# NKK_DOF.net
KiCad netlist of a schematic drawn in Altium Designer
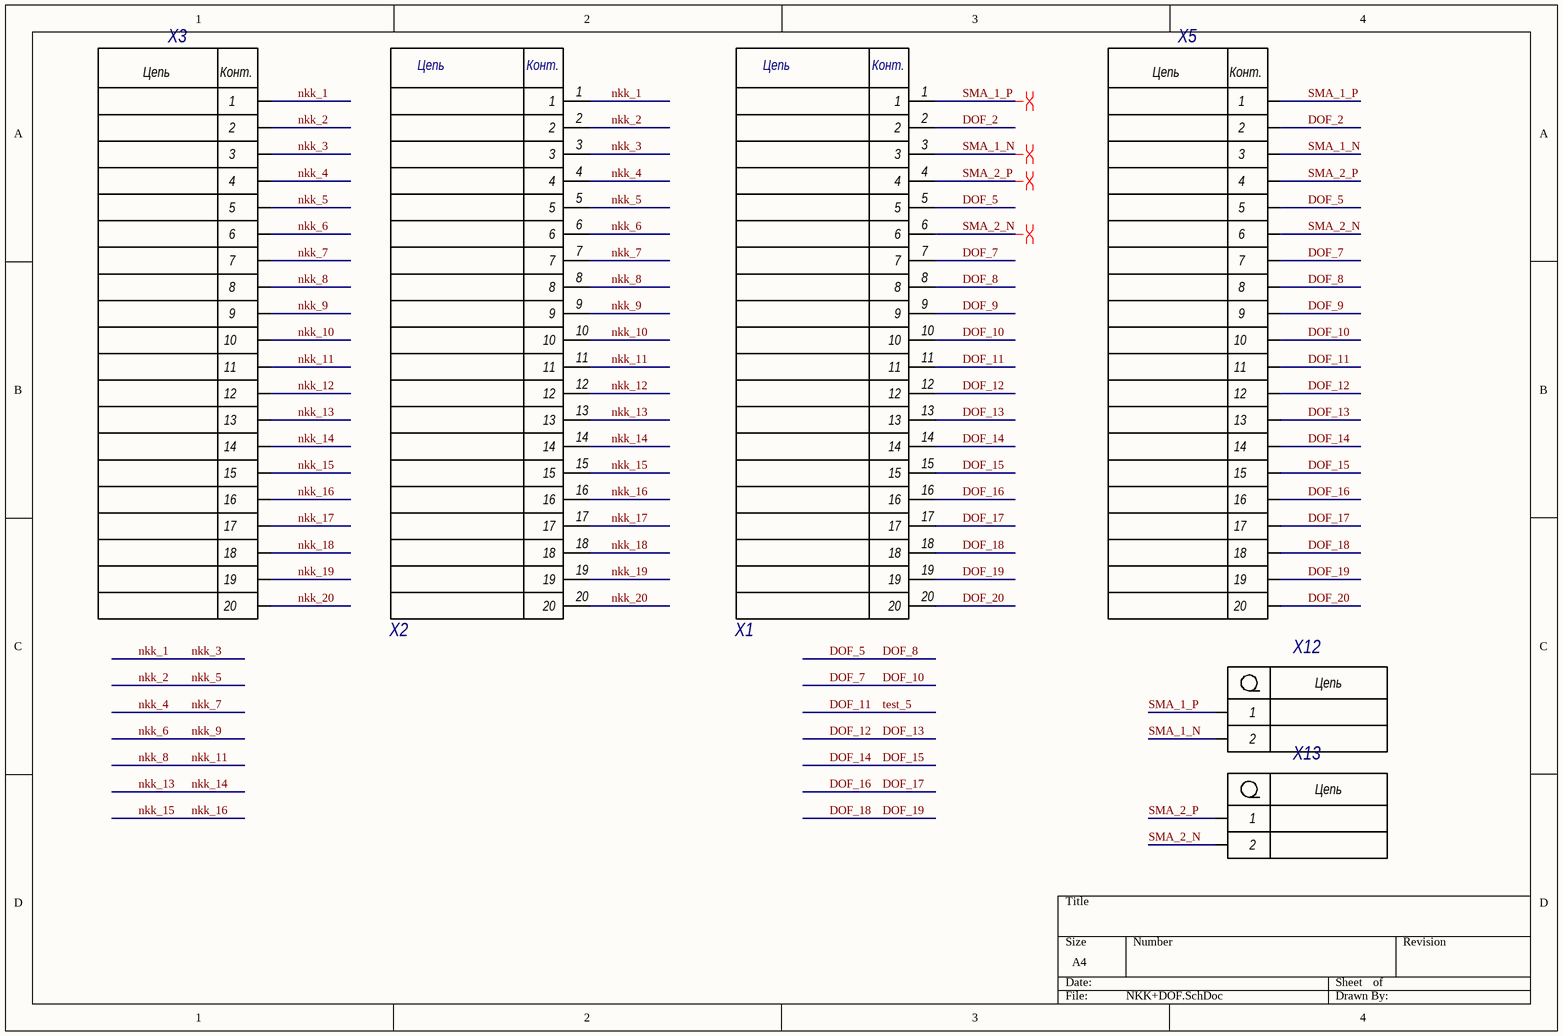
[diagram p0: NKK+DOF.SchDoc]

(export (version "E")
  (design (tool "Eeschema 10.0.6"))
  (components
    (comp (ref "X1")
      (value "2x10")
      (footprint "5011902017")
      (description "CONN HEADER SMD 20POS 1MM")
      (fields (field (name "PARTNUMBER") "5011902017") (field (name "MANUFACTURER") "Molex"))
      (libsource (lib "DatabaseSVN") (part "CON_20"))
    )
    (comp (ref "X2")
      (value "2x10")
      (footprint "5011902017")
      (description "CONN HEADER SMD 20POS 1MM")
      (fields (field (name "PARTNUMBER") "5011902017") (field (name "MANUFACTURER") "Molex"))
      (libsource (lib "DatabaseSVN") (part "CON_20"))
    )
    (comp (ref "X3")
      (value "PLD-20")
      (footprint "PLD-20")
      (description "штыри на плату двурядные")
      (fields (field (name "PARTNUMBER") "PLD-20 2.54mm"))
      (libsource (lib "DatabaseSVN") (part "20_pins"))
    )
    (comp (ref "X5")
      (value "PLD-20")
      (footprint "PLD-20")
      (description "штыри на плату двурядные")
      (fields (field (name "PARTNUMBER") "PLD-20 2.54mm"))
      (libsource (lib "DatabaseSVN") (part "20_pins"))
    )
    (comp (ref "X12")
      (value "SMA JACK")
      (footprint "SMA_THROUGH_HOLE")
      (description "CONN SMA JACK STR 50 OHM PCB")
      (fields (field (name "PARTNUMBER") "WM5543-ND") (field (name "MANUFACTURER") "Molex"))
      (libsource (lib "DatabaseSVN") (part "2_pins_RF"))
    )
    (comp (ref "X13")
      (value "SMA JACK")
      (footprint "SMA_THROUGH_HOLE")
      (description "CONN SMA JACK STR 50 OHM PCB")
      (fields (field (name "PARTNUMBER") "WM5543-ND") (field (name "MANUFACTURER") "Molex"))
      (libsource (lib "DatabaseSVN") (part "2_pins_RF"))
    )
  )
  (nets
    (net (code "1") (name "/DOF_2") (class "Default")
      (node (ref "X1") (pin "2") (pinfunction "2_2") (pintype "passive"))
      (node (ref "X5") (pin "2") (pinfunction "2_2") (pintype "passive"))
    )
    (net (code "2") (name "/DOF_5") (class "Default")
      (node (ref "X1") (pin "5") (pinfunction "5_5") (pintype "passive"))
      (node (ref "X1") (pin "8") (pinfunction "8_8") (pintype "passive"))
      (node (ref "X5") (pin "5") (pinfunction "5_5") (pintype "passive"))
      (node (ref "X5") (pin "8") (pinfunction "8_8") (pintype "passive"))
    )
    (net (code "3") (name "/DOF_9") (class "Default")
      (node (ref "X1") (pin "9") (pinfunction "9_9") (pintype "passive"))
      (node (ref "X5") (pin "9") (pinfunction "9_9") (pintype "passive"))
    )
    (net (code "4") (name "/DOF_10") (class "Default")
      (node (ref "X1") (pin "10") (pinfunction "10_10") (pintype "passive"))
      (node (ref "X1") (pin "7") (pinfunction "7_7") (pintype "passive"))
      (node (ref "X5") (pin "10") (pinfunction "10_10") (pintype "passive"))
      (node (ref "X5") (pin "7") (pinfunction "7_7") (pintype "passive"))
    )
    (net (code "5") (name "/DOF_11") (class "Default")
      (node (ref "X1") (pin "11") (pinfunction "11_11") (pintype "passive"))
      (node (ref "X5") (pin "11") (pinfunction "11_11") (pintype "passive"))
    )
    (net (code "6") (name "/DOF_12") (class "Default")
      (node (ref "X1") (pin "12") (pinfunction "12_12") (pintype "passive"))
      (node (ref "X1") (pin "13") (pinfunction "13_13") (pintype "passive"))
      (node (ref "X5") (pin "12") (pinfunction "12_12") (pintype "passive"))
      (node (ref "X5") (pin "13") (pinfunction "13_13") (pintype "passive"))
    )
    (net (code "7") (name "/DOF_14") (class "Default")
      (node (ref "X1") (pin "14") (pinfunction "14_14") (pintype "passive"))
      (node (ref "X1") (pin "15") (pinfunction "15_15") (pintype "passive"))
      (node (ref "X5") (pin "14") (pinfunction "14_14") (pintype "passive"))
      (node (ref "X5") (pin "15") (pinfunction "15_15") (pintype "passive"))
    )
    (net (code "8") (name "/DOF_16") (class "Default")
      (node (ref "X1") (pin "16") (pinfunction "16_16") (pintype "passive"))
      (node (ref "X1") (pin "17") (pinfunction "17_17") (pintype "passive"))
      (node (ref "X5") (pin "16") (pinfunction "16_16") (pintype "passive"))
      (node (ref "X5") (pin "17") (pinfunction "17_17") (pintype "passive"))
    )
    (net (code "9") (name "/DOF_18") (class "Default")
      (node (ref "X1") (pin "18") (pinfunction "18_18") (pintype "passive"))
      (node (ref "X1") (pin "19") (pinfunction "19_19") (pintype "passive"))
      (node (ref "X5") (pin "18") (pinfunction "18_18") (pintype "passive"))
      (node (ref "X5") (pin "19") (pinfunction "19_19") (pintype "passive"))
    )
    (net (code "10") (name "/DOF_20") (class "Default")
      (node (ref "X1") (pin "20") (pinfunction "20_20") (pintype "passive"))
      (node (ref "X5") (pin "20") (pinfunction "20_20") (pintype "passive"))
    )
    (net (code "11") (name "/SMA_1_N") (class "Default")
      (node (ref "X1") (pin "3") (pinfunction "3_3") (pintype "passive"))
      (node (ref "X12") (pin "2") (pinfunction "2_2") (pintype "passive"))
      (node (ref "X5") (pin "3") (pinfunction "3_3") (pintype "passive"))
    )
    (net (code "12") (name "/SMA_1_P") (class "Default")
      (node (ref "X1") (pin "1") (pinfunction "1_1") (pintype "passive"))
      (node (ref "X12") (pin "1") (pinfunction "1_1") (pintype "passive"))
      (node (ref "X5") (pin "1") (pinfunction "1_1") (pintype "passive"))
    )
    (net (code "13") (name "/SMA_2_N") (class "Default")
      (node (ref "X1") (pin "6") (pinfunction "6_6") (pintype "passive"))
      (node (ref "X13") (pin "2") (pinfunction "2_2") (pintype "passive"))
      (node (ref "X5") (pin "6") (pinfunction "6_6") (pintype "passive"))
    )
    (net (code "14") (name "/SMA_2_P") (class "Default")
      (node (ref "X1") (pin "4") (pinfunction "4_4") (pintype "passive"))
      (node (ref "X13") (pin "1") (pinfunction "1_1") (pintype "passive"))
      (node (ref "X5") (pin "4") (pinfunction "4_4") (pintype "passive"))
    )
    (net (code "15") (name "/nkk_1") (class "Default")
      (node (ref "X2") (pin "1") (pinfunction "1_1") (pintype "passive"))
      (node (ref "X2") (pin "3") (pinfunction "3_3") (pintype "passive"))
      (node (ref "X3") (pin "1") (pinfunction "1_1") (pintype "passive"))
      (node (ref "X3") (pin "3") (pinfunction "3_3") (pintype "passive"))
    )
    (net (code "16") (name "/nkk_2") (class "Default")
      (node (ref "X2") (pin "2") (pinfunction "2_2") (pintype "passive"))
      (node (ref "X2") (pin "5") (pinfunction "5_5") (pintype "passive"))
      (node (ref "X3") (pin "2") (pinfunction "2_2") (pintype "passive"))
      (node (ref "X3") (pin "5") (pinfunction "5_5") (pintype "passive"))
    )
    (net (code "17") (name "/nkk_4") (class "Default")
      (node (ref "X2") (pin "4") (pinfunction "4_4") (pintype "passive"))
      (node (ref "X2") (pin "7") (pinfunction "7_7") (pintype "passive"))
      (node (ref "X3") (pin "4") (pinfunction "4_4") (pintype "passive"))
      (node (ref "X3") (pin "7") (pinfunction "7_7") (pintype "passive"))
    )
    (net (code "18") (name "/nkk_6") (class "Default")
      (node (ref "X2") (pin "6") (pinfunction "6_6") (pintype "passive"))
      (node (ref "X2") (pin "9") (pinfunction "9_9") (pintype "passive"))
      (node (ref "X3") (pin "6") (pinfunction "6_6") (pintype "passive"))
      (node (ref "X3") (pin "9") (pinfunction "9_9") (pintype "passive"))
    )
    (net (code "19") (name "/nkk_10") (class "Default")
      (node (ref "X2") (pin "10") (pinfunction "10_10") (pintype "passive"))
      (node (ref "X3") (pin "10") (pinfunction "10_10") (pintype "passive"))
    )
    (net (code "20") (name "/nkk_11") (class "Default")
      (node (ref "X2") (pin "11") (pinfunction "11_11") (pintype "passive"))
      (node (ref "X2") (pin "8") (pinfunction "8_8") (pintype "passive"))
      (node (ref "X3") (pin "11") (pinfunction "11_11") (pintype "passive"))
      (node (ref "X3") (pin "8") (pinfunction "8_8") (pintype "passive"))
    )
    (net (code "21") (name "/nkk_12") (class "Default")
      (node (ref "X2") (pin "12") (pinfunction "12_12") (pintype "passive"))
      (node (ref "X3") (pin "12") (pinfunction "12_12") (pintype "passive"))
    )
    (net (code "22") (name "/nkk_13") (class "Default")
      (node (ref "X2") (pin "13") (pinfunction "13_13") (pintype "passive"))
      (node (ref "X2") (pin "14") (pinfunction "14_14") (pintype "passive"))
      (node (ref "X3") (pin "13") (pinfunction "13_13") (pintype "passive"))
      (node (ref "X3") (pin "14") (pinfunction "14_14") (pintype "passive"))
    )
    (net (code "23") (name "/nkk_15") (class "Default")
      (node (ref "X2") (pin "15") (pinfunction "15_15") (pintype "passive"))
      (node (ref "X2") (pin "16") (pinfunction "16_16") (pintype "passive"))
      (node (ref "X3") (pin "15") (pinfunction "15_15") (pintype "passive"))
      (node (ref "X3") (pin "16") (pinfunction "16_16") (pintype "passive"))
    )
    (net (code "24") (name "/nkk_17") (class "Default")
      (node (ref "X2") (pin "17") (pinfunction "17_17") (pintype "passive"))
      (node (ref "X3") (pin "17") (pinfunction "17_17") (pintype "passive"))
    )
    (net (code "25") (name "/nkk_18") (class "Default")
      (node (ref "X2") (pin "18") (pinfunction "18_18") (pintype "passive"))
      (node (ref "X3") (pin "18") (pinfunction "18_18") (pintype "passive"))
    )
    (net (code "26") (name "/nkk_19") (class "Default")
      (node (ref "X2") (pin "19") (pinfunction "19_19") (pintype "passive"))
      (node (ref "X3") (pin "19") (pinfunction "19_19") (pintype "passive"))
    )
    (net (code "27") (name "/nkk_20") (class "Default")
      (node (ref "X2") (pin "20") (pinfunction "20_20") (pintype "passive"))
      (node (ref "X3") (pin "20") (pinfunction "20_20") (pintype "passive"))
    )
  )
)
